# design.net
KiCad netlist of a schematic drawn in Altium Designer
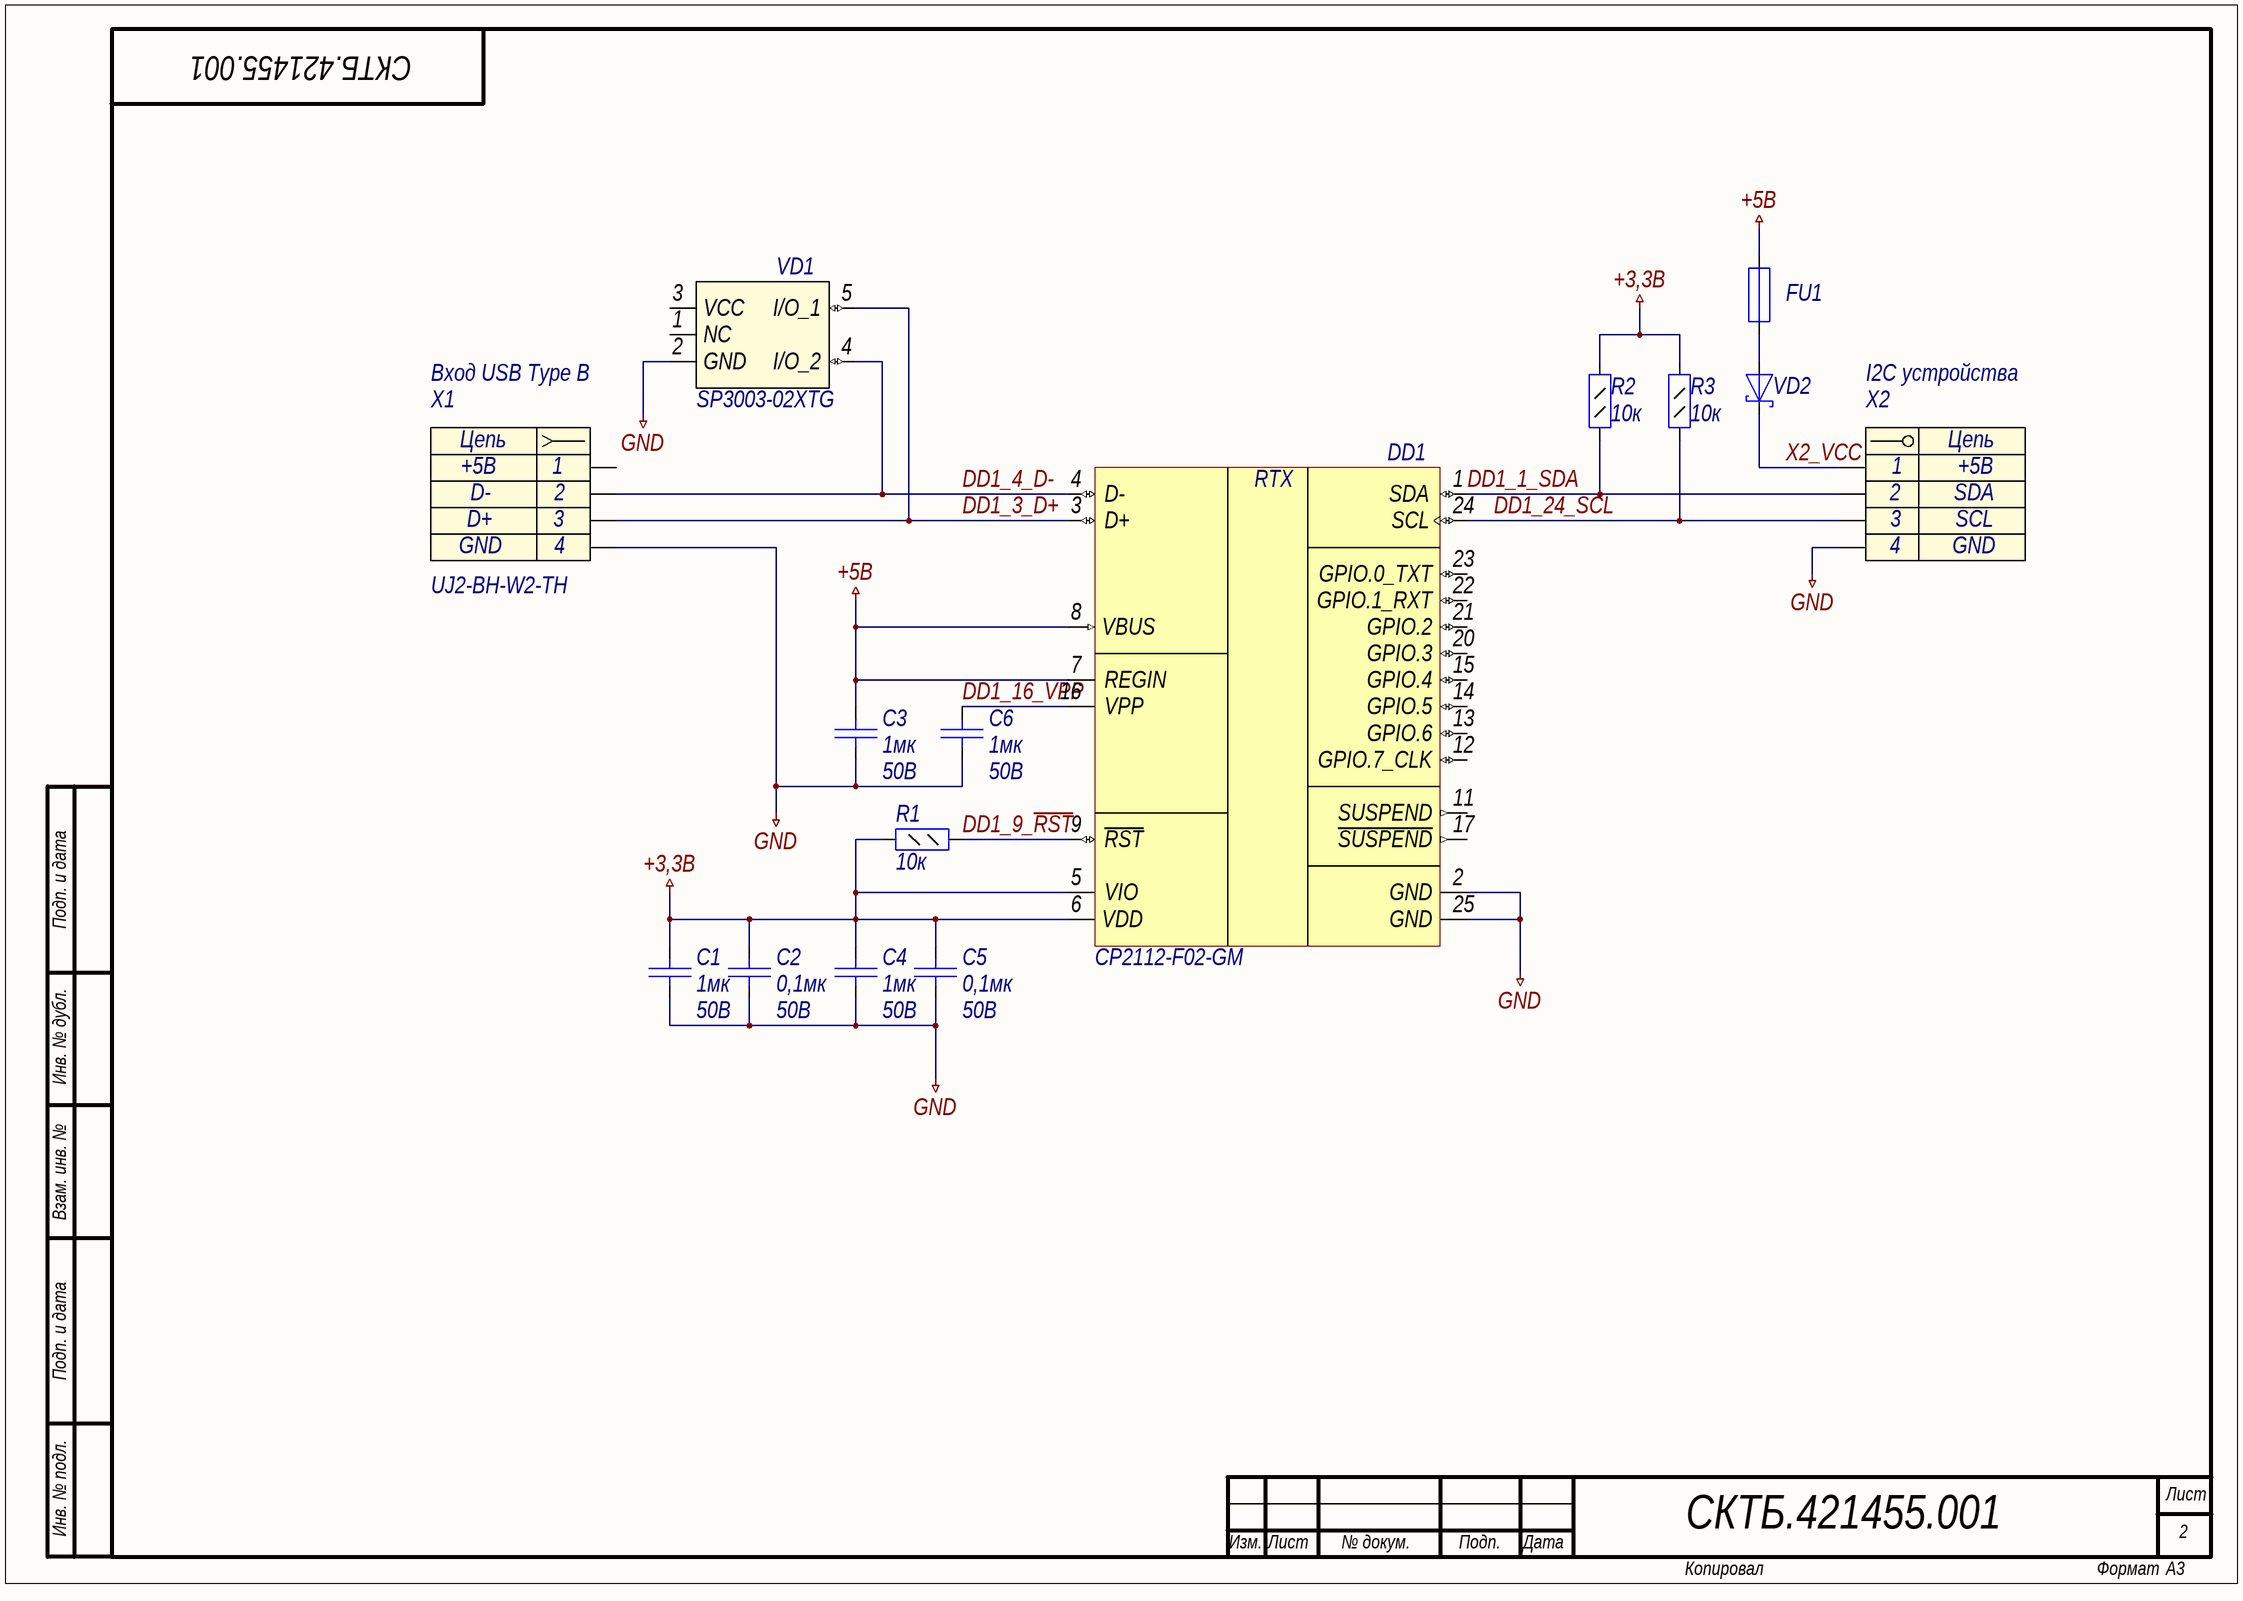
[diagram p0: Преобразователь интерфейсов.SchDoc]

(export (version "E")
  (design (tool "Eeschema 10.0.6"))
  (components
    (comp (ref "C1")
      (value "1мк")
      (footprint "C0603")
      (description "Конденсатор")
      (fields
        (field (name "VOLTAGE") "50B")
        (field (name "PART NUMBER") "GRM188R71C105KA12D**")
        (field (name "Comment") "Capacitor")
      )
      (libsource (lib "MOP44") (part "Capacitor"))
    )
    (comp (ref "C2")
      (value "0,1мк")
      (footprint "C0603")
      (description "Конденсатор")
      (fields
        (field (name "VOLTAGE") "50B")
        (field (name "PART NUMBER") "GRM188R71H104K")
        (field (name "Comment") "Capacitor")
      )
      (libsource (lib "MOP44") (part "Capacitor"))
    )
    (comp (ref "C3")
      (value "1мк")
      (footprint "C0603")
      (description "Конденсатор")
      (fields
        (field (name "VOLTAGE") "50B")
        (field (name "PART NUMBER") "GRM188R71C105KA12D**")
        (field (name "Comment") "Capacitor")
      )
      (libsource (lib "MOP44") (part "Capacitor"))
    )
    (comp (ref "C4")
      (value "1мк")
      (footprint "C0603")
      (description "Конденсатор")
      (fields
        (field (name "VOLTAGE") "50B")
        (field (name "PART NUMBER") "GRM188R71C105KA12D**")
        (field (name "Comment") "Capacitor")
      )
      (libsource (lib "MOP44") (part "Capacitor"))
    )
    (comp (ref "C5")
      (value "0,1мк")
      (footprint "C0603")
      (description "Конденсатор")
      (fields
        (field (name "VOLTAGE") "50B")
        (field (name "PART NUMBER") "GRM188R71H104K")
        (field (name "Comment") "Capacitor")
      )
      (libsource (lib "MOP44") (part "Capacitor"))
    )
    (comp (ref "C6")
      (value "1мк")
      (footprint "C0603")
      (description "Конденсатор")
      (fields
        (field (name "VOLTAGE") "50B")
        (field (name "PART NUMBER") "GRM188R71C105KA12D**")
        (field (name "Comment") "Capacitor")
      )
      (libsource (lib "MOP44") (part "Capacitor"))
    )
    (comp (ref "DD1")
      (value "CP2112-F02-GM")
      (footprint "QFN24")
      (description "USB-I2C преобразователь")
      (libsource (lib "MOP44") (part "CP2112-F02-GM"))
    )
    (comp (ref "FU1")
      (value "Fuse")
      (footprint "FUSE812")
      (description "Предохранитель")
      (fields (field (name "PART NUMBER") "MF-USMF005-2"))
      (libsource (lib "MOP44") (part "Fuse"))
    )
    (comp (ref "R1")
      (value "10к")
      (footprint "R0805")
      (description "Резистор")
      (fields (field (name "PART NUMBER") "RC0805FR-0710KL") (field (name "POWER") "0,125Вт"))
      (libsource (lib "") (part "Resistor_0,125Вт_1"))
    )
    (comp (ref "R2")
      (value "10к")
      (footprint "R0805")
      (description "Резистор")
      (fields (field (name "PART NUMBER") "RC0805FR-0710KL") (field (name "POWER") "0,125Вт"))
      (libsource (lib "MOP44") (part "Resistor_0,125Вт"))
    )
    (comp (ref "R3")
      (value "10к")
      (footprint "R0805")
      (description "Резистор")
      (fields (field (name "PART NUMBER") "RC0805FR-0710KL") (field (name "POWER") "0,125Вт"))
      (libsource (lib "MOP44") (part "Resistor_0,125Вт"))
    )
    (comp (ref "VD1")
      (value "SP3003-02XTG")
      (footprint "SOT553")
      (description "Двухканальная ESD защита USB")
      (libsource (lib "MOP44") (part "SP3003-02XTG"))
    )
    (comp (ref "VD2")
      (value "DiodeSchottky")
      (footprint "SMA")
      (description "Диод Шоттки")
      (fields (field (name "PART NUMBER") "SK34A"))
      (libsource (lib "MOP44") (part "DiodeSchottky"))
    )
    (comp (ref "X1")
      (value "Вход USB Type B")
      (footprint "USB-B RECEPTACLE")
      (description "Разъем - 4 конт. розетка")
      (fields (field (name "PART NUMBER") "UJ2-BH-W2-TH"))
      (libsource (lib "MOP44") (part "Header_4_sct"))
    )
    (comp (ref "X2")
      (value "I2C устройства")
      (footprint "TERMINAL 4 way-5mm")
      (description "Разъем - 4 конт. клеммник")
      (libsource (lib "MOP44") (part "Header_4_trm"))
    )
  )
  (nets
    (net (code "1") (name "+3,3В") (class "Default")
      (node (ref "C1") (pin "2") (pinfunction "2_2") (pintype "passive"))
      (node (ref "C2") (pin "2") (pinfunction "2_2") (pintype "passive"))
      (node (ref "C4") (pin "2") (pinfunction "2_2") (pintype "passive"))
      (node (ref "C5") (pin "2") (pinfunction "2_2") (pintype "passive"))
      (node (ref "DD1") (pin "5") (pinfunction "VIO_5") (pintype "power_in"))
      (node (ref "DD1") (pin "6") (pinfunction "VDD_6") (pintype "power_in"))
      (node (ref "R1") (pin "2") (pinfunction "2_2") (pintype "passive"))
      (node (ref "R2") (pin "2") (pinfunction "2_2") (pintype "passive"))
      (node (ref "R3") (pin "2") (pinfunction "2_2") (pintype "passive"))
    )
    (net (code "2") (name "+5В") (class "Default")
      (node (ref "C3") (pin "2") (pinfunction "2_2") (pintype "passive"))
      (node (ref "DD1") (pin "7") (pinfunction "REGIN_7") (pintype "power_in"))
      (node (ref "DD1") (pin "8") (pinfunction "VBUS_8") (pintype "input"))
      (node (ref "FU1") (pin "2") (pinfunction "2_2") (pintype "passive"))
    )
    (net (code "3") (name "/DD1_1_SDA") (class "Default")
      (node (ref "DD1") (pin "1") (pinfunction "SDA_1") (pintype "bidirectional"))
      (node (ref "R2") (pin "1") (pinfunction "1_1") (pintype "passive"))
      (node (ref "X2") (pin "2") (pinfunction "2_2") (pintype "passive"))
    )
    (net (code "4") (name "/DD1_3_D+") (class "Default")
      (node (ref "DD1") (pin "3") (pinfunction "D+_3") (pintype "bidirectional"))
      (node (ref "VD1") (pin "5") (pinfunction "I/O_1_5") (pintype "bidirectional"))
      (node (ref "X1") (pin "3") (pinfunction "3_3") (pintype "passive"))
    )
    (net (code "5") (name "/DD1_4_D-") (class "Default")
      (node (ref "DD1") (pin "4") (pinfunction "D-_4") (pintype "bidirectional"))
      (node (ref "VD1") (pin "4") (pinfunction "I/O_2_4") (pintype "bidirectional"))
      (node (ref "X1") (pin "2") (pinfunction "2_2") (pintype "passive"))
    )
    (net (code "6") (name "/DD1_9_~{RST}") (class "Default")
      (node (ref "DD1") (pin "9") (pinfunction "~{RST}_9") (pintype "bidirectional"))
      (node (ref "R1") (pin "1") (pinfunction "1_1") (pintype "passive"))
    )
    (net (code "7") (name "/DD1_16_VPP") (class "Default")
      (node (ref "C6") (pin "2") (pinfunction "2_2") (pintype "passive"))
      (node (ref "DD1") (pin "16") (pinfunction "VPP_16") (pintype "passive"))
    )
    (net (code "8") (name "/DD1_24_SCL") (class "Default")
      (node (ref "DD1") (pin "24") (pinfunction "SCL_24") (pintype "bidirectional"))
      (node (ref "R3") (pin "1") (pinfunction "1_1") (pintype "passive"))
      (node (ref "X2") (pin "3") (pinfunction "3_3") (pintype "passive"))
    )
    (net (code "9") (name "/X2_VCC") (class "Default")
      (node (ref "VD2") (pin "1") (pinfunction "K_1") (pintype "passive"))
      (node (ref "X2") (pin "1") (pinfunction "1_1") (pintype "passive"))
    )
    (net (code "10") (name "GND") (class "Default")
      (node (ref "C1") (pin "1") (pinfunction "1_1") (pintype "passive"))
      (node (ref "C2") (pin "1") (pinfunction "1_1") (pintype "passive"))
      (node (ref "C3") (pin "1") (pinfunction "1_1") (pintype "passive"))
      (node (ref "C4") (pin "1") (pinfunction "1_1") (pintype "passive"))
      (node (ref "C5") (pin "1") (pinfunction "1_1") (pintype "passive"))
      (node (ref "C6") (pin "1") (pinfunction "1_1") (pintype "passive"))
      (node (ref "DD1") (pin "2") (pinfunction "GND_2") (pintype "power_in"))
      (node (ref "DD1") (pin "25") (pinfunction "GND_25") (pintype "power_in"))
      (node (ref "VD1") (pin "2") (pinfunction "GND_2") (pintype "passive"))
      (node (ref "X1") (pin "4") (pinfunction "4_4") (pintype "passive"))
      (node (ref "X2") (pin "4") (pinfunction "4_4") (pintype "passive"))
    )
    (net (code "11") (name "Net-(VD2-A)") (class "Default")
      (node (ref "FU1") (pin "1") (pinfunction "1_1") (pintype "passive"))
      (node (ref "VD2") (pin "2") (pinfunction "A_2") (pintype "passive"))
    )
    (net (code "12") (name "unconnected-(DD1-GPIO.0_TXT-Pad23)") (class "Default")
      (node (ref "DD1") (pin "23") (pinfunction "GPIO.0_TXT_23") (pintype "bidirectional"))
    )
    (net (code "13") (name "unconnected-(DD1-GPIO.1_RXT-Pad22)") (class "Default")
      (node (ref "DD1") (pin "22") (pinfunction "GPIO.1_RXT_22") (pintype "bidirectional"))
    )
    (net (code "14") (name "unconnected-(DD1-GPIO.2-Pad21)") (class "Default")
      (node (ref "DD1") (pin "21") (pinfunction "GPIO.2_21") (pintype "bidirectional"))
    )
    (net (code "15") (name "unconnected-(DD1-GPIO.3-Pad20)") (class "Default")
      (node (ref "DD1") (pin "20") (pinfunction "GPIO.3_20") (pintype "bidirectional"))
    )
    (net (code "16") (name "unconnected-(DD1-GPIO.4-Pad15)") (class "Default")
      (node (ref "DD1") (pin "15") (pinfunction "GPIO.4_15") (pintype "bidirectional"))
    )
    (net (code "17") (name "unconnected-(DD1-GPIO.5-Pad14)") (class "Default")
      (node (ref "DD1") (pin "14") (pinfunction "GPIO.5_14") (pintype "bidirectional"))
    )
    (net (code "18") (name "unconnected-(DD1-GPIO.6-Pad13)") (class "Default")
      (node (ref "DD1") (pin "13") (pinfunction "GPIO.6_13") (pintype "bidirectional"))
    )
    (net (code "19") (name "unconnected-(DD1-GPIO.7_CLK-Pad12)") (class "Default")
      (node (ref "DD1") (pin "12") (pinfunction "GPIO.7_CLK_12") (pintype "bidirectional"))
    )
    (net (code "20") (name "unconnected-(DD1-SUSPEND-Pad11)") (class "Default")
      (node (ref "DD1") (pin "11") (pinfunction "SUSPEND_11") (pintype "output"))
    )
    (net (code "21") (name "unconnected-(DD1-~{SUSPEND}-Pad17)") (class "Default")
      (node (ref "DD1") (pin "17") (pinfunction "~{SUSPEND}_17") (pintype "output"))
    )
    (net (code "22") (name "unconnected-(VD1-NC-Pad1)") (class "Default")
      (node (ref "VD1") (pin "1") (pinfunction "NC_1") (pintype "passive"))
    )
    (net (code "23") (name "unconnected-(VD1-VCC-Pad3)") (class "Default")
      (node (ref "VD1") (pin "3") (pinfunction "VCC_3") (pintype "power_in"))
    )
    (net (code "24") (name "unconnected-(X1-Pad1)") (class "Default")
      (node (ref "X1") (pin "1") (pinfunction "1_1") (pintype "passive"))
    )
  )
)
